# Signal_Conditioning_1.net
KiCad netlist of a schematic drawn in Altium Designer
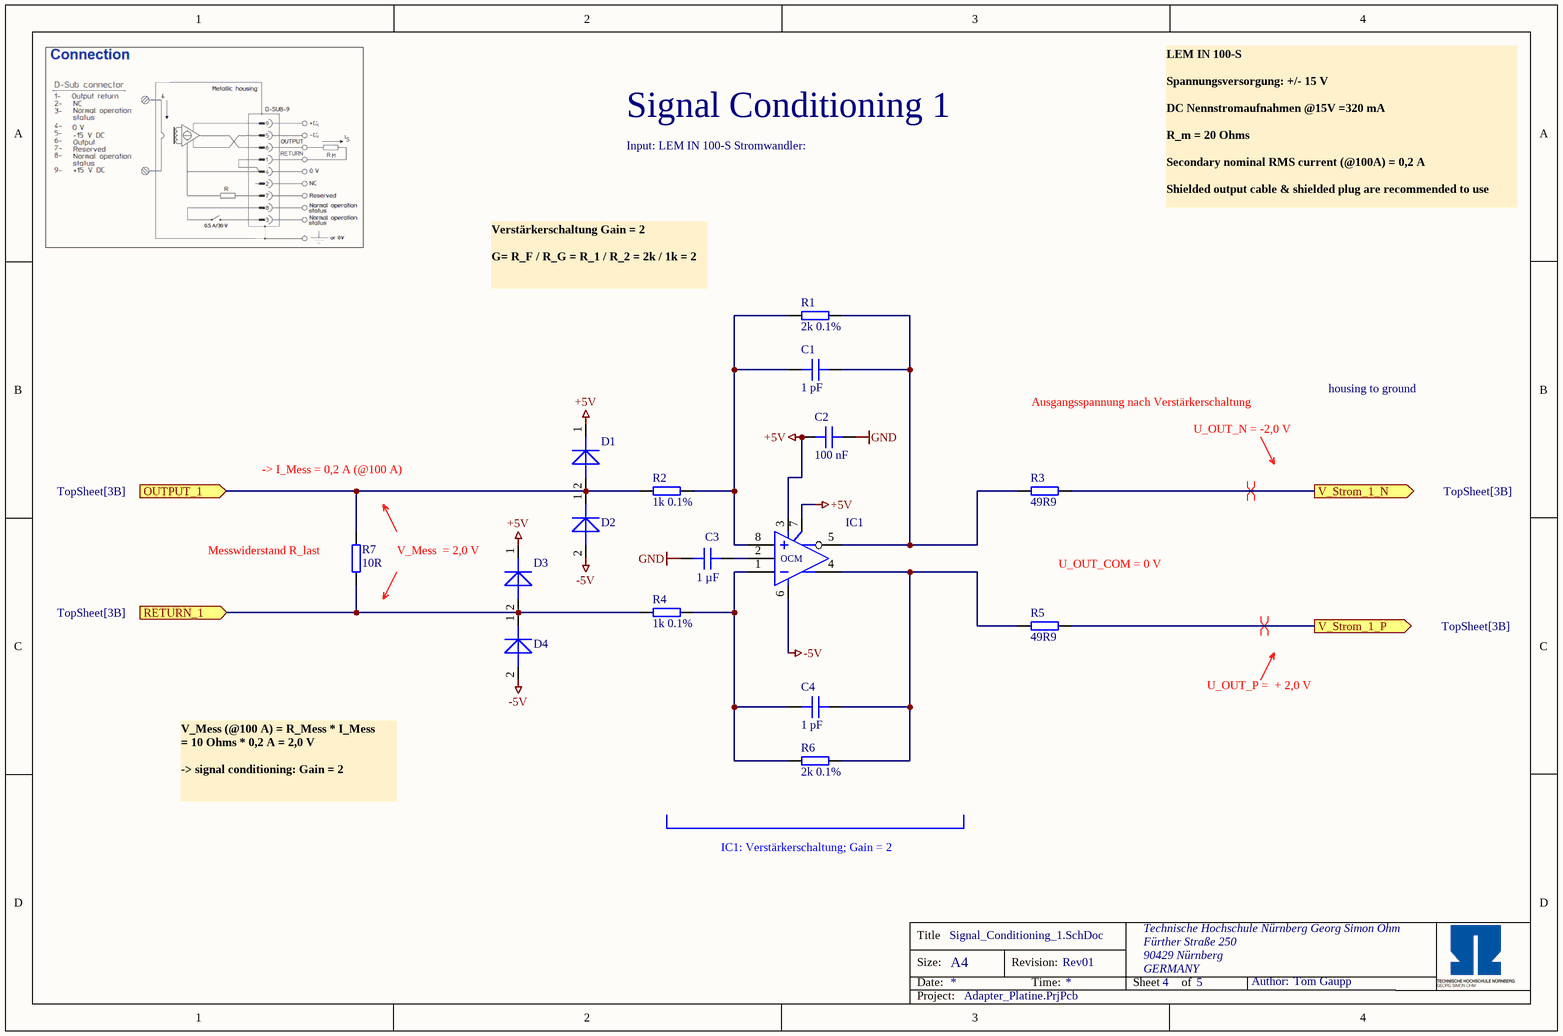
[diagram p0: Signal_Conditioning_1.SchDoc]

(export (version "E")
  (design (tool "Eeschema 10.0.6"))
  (components
    (comp (ref "C1")
      (value "1 pF")
      (footprint "C_0603")
      (description "Multilayer Ceramic Capacitors MLCC - SMD/SMT 50V 1pF C0G 0603 +/-.1pF")
      (fields
        (field (name "MANUFACTURER PART NUMBER") "KGM15ACG1H1R0BT")
        (field (name "MANUFACTURER") "KYOCERA AVX")
        (field (name "CREATED FROM") "TGaupp")
      )
      (libsource (lib "user") (part "Capacitor"))
    )
    (comp (ref "C2")
      (value "100 nF")
      (footprint "C_0603")
      (description "Capacitor 0603, 6.3 VDC, 100 nF, X5R")
      (fields
        (field (name "MANUFACTURER PART NUMBER") "C0603C104K9PACTU")
        (field (name "MANUFACTURER") "KEMET")
        (field (name "CREATED FROM") "MGremer")
      )
      (libsource (lib "user") (part "Capacitor"))
    )
    (comp (ref "C3")
      (value "1 µF")
      (footprint "C_0603")
      (description "50V 1uF X5R ±10% 0603  Multilayer Ceramic Capacitors MLCC - SMD/SMT ROHS")
      (fields
        (field (name "MANUFACTURER") "Samsung Electro-Mechanics")
        (field (name "MANUFACTURER PART NUMBER") "CL10A105KB8NNNC")
        (field (name "CREATED FROM") "MGremer")
      )
      (libsource (lib "user") (part "Capacitor"))
    )
    (comp (ref "C4")
      (value "1 pF")
      (footprint "C_0603")
      (description "Multilayer Ceramic Capacitors MLCC - SMD/SMT 50V 1pF C0G 0603 +/-.1pF")
      (fields
        (field (name "MANUFACTURER PART NUMBER") "KGM15ACG1H1R0BT")
        (field (name "MANUFACTURER") "KYOCERA AVX")
        (field (name "CREATED FROM") "TGaupp")
      )
      (libsource (lib "user") (part "Capacitor"))
    )
    (comp (ref "D1")
      (value "1SS356VMFHTE-17")
      (footprint "eigene_lib_alt:1SS356VMFHTE17")
      (description "Diode")
      (fields (field (name "MOUSER PART NUMBER") "755-1SS356VMFHTE-17"))
      (libsource (lib "SamacSys") (part "1SS356VMFHTE-17"))
    )
    (comp (ref "D2")
      (value "1SS356VMFHTE-17")
      (footprint "eigene_lib_alt:1SS356VMFHTE17")
      (description "Diode")
      (fields (field (name "MOUSER PART NUMBER") "755-1SS356VMFHTE-17"))
      (libsource (lib "SamacSys") (part "1SS356VMFHTE-17"))
    )
    (comp (ref "D3")
      (value "1SS356VMFHTE-17")
      (footprint "eigene_lib_alt:1SS356VMFHTE17")
      (description "Diode")
      (fields (field (name "MOUSER PART NUMBER") "755-1SS356VMFHTE-17"))
      (libsource (lib "SamacSys") (part "1SS356VMFHTE-17"))
    )
    (comp (ref "D4")
      (value "1SS356VMFHTE-17")
      (footprint "eigene_lib_alt:1SS356VMFHTE17")
      (description "Diode")
      (fields (field (name "MOUSER PART NUMBER") "755-1SS356VMFHTE-17"))
      (libsource (lib "SamacSys") (part "1SS356VMFHTE-17"))
    )
    (comp (ref "IC1")
      (value "ADA4940-1ARZ-R7")
      (footprint "SOIC-8-N")
      (description "Differential ADC Driver")
      (fields (field (name "MANUFACTURER") "Analog Devices") (field (name "CREATED FROM") "MGremer"))
      (libsource (lib "user") (part "ADA4940-1ARZ"))
    )
    (comp (ref "R1")
      (value "2k 0.1%")
      (footprint "RES 1206_3216")
      (description "SMD resistor 2Kohms .1% 400mW 25ppm")
      (fields
        (field (name "MANUFACTURER PART NUMBER") "TNPW12062K00BEEA")
        (field (name "MANUFACTURER") "Vishay")
        (field (name "CREATED FROM") "TGaupp")
      )
      (libsource (lib "user") (part "Resistor"))
    )
    (comp (ref "R2")
      (value "1k 0.1%")
      (footprint "RES 1206_3216")
      (description "SMD resistor 1/4W 1.0Kohm 0.1% 25ppm")
      (fields
        (field (name "MANUFACTURER PART NUMBER") "ERA-8AEB102V")
        (field (name "MANUFACTURER") "Panasonic")
        (field (name "CREATED FROM") "TGaupp")
      )
      (libsource (lib "user") (part "Resistor"))
    )
    (comp (ref "R3")
      (value "49R9")
      (footprint "RES 0603_1608")
      (description "100mW Thick Film Resistors ±100ppm/℃ ±1% 49.9Ω 0603 Chip Resistor - Surface Mount ROHS")
      (fields
        (field (name "MANUFACTURER PART NUMBER") "RC0603FR-0749R9L")
        (field (name "MANUFACTURER") "YAGEO")
        (field (name "CREATED FROM") "AGeiger")
      )
      (libsource (lib "user") (part "Resistor"))
    )
    (comp (ref "R4")
      (value "1k 0.1%")
      (footprint "RES 1206_3216")
      (description "SMD resistor 1/4W 1.0Kohm 0.1% 25ppm")
      (fields
        (field (name "MANUFACTURER PART NUMBER") "ERA-8AEB102V")
        (field (name "MANUFACTURER") "Panasonic")
        (field (name "CREATED FROM") "TGaupp")
      )
      (libsource (lib "user") (part "Resistor"))
    )
    (comp (ref "R5")
      (value "49R9")
      (footprint "RES 0603_1608")
      (description "100mW Thick Film Resistors ±100ppm/℃ ±1% 49.9Ω 0603 Chip Resistor - Surface Mount ROHS")
      (fields
        (field (name "MANUFACTURER PART NUMBER") "RC0603FR-0749R9L")
        (field (name "MANUFACTURER") "YAGEO")
        (field (name "CREATED FROM") "AGeiger")
      )
      (libsource (lib "user") (part "Resistor"))
    )
    (comp (ref "R6")
      (value "2k 0.1%")
      (footprint "RES 1206_3216")
      (description "SMD resistor 2Kohms .1% 400mW 25ppm")
      (fields
        (field (name "MANUFACTURER PART NUMBER") "TNPW12062K00BEEA")
        (field (name "MANUFACTURER") "Vishay")
        (field (name "CREATED FROM") "TGaupp")
      )
      (libsource (lib "user") (part "Resistor"))
    )
    (comp (ref "R7")
      (value "10R")
      (footprint "RES 1206_3216")
      (description "SMD 10 ohm 0.5% 0.5W")
      (fields
        (field (name "MANUFACTURER PART NUMBER") "SG73G2BTTD10R0D")
        (field (name "MANUFACTURER") "KOA Speer")
        (field (name "CREATED FROM") "TGaupp")
      )
      (libsource (lib "user") (part "Resistor"))
    )
  )
  (nets
    (net (code "1") (name "+5V") (class "Default")
      (node (ref "C2") (pin "1") (pinfunction "1_1") (pintype "passive"))
      (node (ref "D1") (pin "1") (pinfunction "K_1") (pintype "passive"))
      (node (ref "D3") (pin "1") (pinfunction "K_1") (pintype "passive"))
      (node (ref "IC1") (pin "3") (pinfunction "V+_3") (pintype "passive"))
      (node (ref "IC1") (pin "7") (pinfunction "EN_7") (pintype "passive"))
    )
    (net (code "2") (name "-5V") (class "Default")
      (node (ref "D2") (pin "2") (pinfunction "A_2") (pintype "passive"))
      (node (ref "D4") (pin "2") (pinfunction "A_2") (pintype "passive"))
      (node (ref "IC1") (pin "6") (pinfunction "V-_6") (pintype "passive"))
    )
    (net (code "3") (name "/OUTPUT_1") (class "Default")
      (node (ref "D1") (pin "2") (pinfunction "A_2") (pintype "passive"))
      (node (ref "D2") (pin "1") (pinfunction "K_1") (pintype "passive"))
      (node (ref "R2") (pin "1") (pinfunction "1_1") (pintype "passive"))
      (node (ref "R7") (pin "2") (pinfunction "2_2") (pintype "passive"))
    )
    (net (code "4") (name "/RETURN_1") (class "Default")
      (node (ref "D3") (pin "2") (pinfunction "A_2") (pintype "passive"))
      (node (ref "D4") (pin "1") (pinfunction "K_1") (pintype "passive"))
      (node (ref "R4") (pin "1") (pinfunction "1_1") (pintype "passive"))
      (node (ref "R7") (pin "1") (pinfunction "1_1") (pintype "passive"))
    )
    (net (code "5") (name "/V_Strom_1_N") (class "Default")
      (node (ref "R3") (pin "2") (pinfunction "2_2") (pintype "passive"))
    )
    (net (code "6") (name "/V_Strom_1_P") (class "Default")
      (node (ref "R5") (pin "2") (pinfunction "2_2") (pintype "passive"))
    )
    (net (code "7") (name "GND") (class "Default")
      (node (ref "C2") (pin "2") (pinfunction "2_2") (pintype "passive"))
      (node (ref "C3") (pin "1") (pinfunction "1_1") (pintype "passive"))
    )
    (net (code "8") (name "Net-(C1-Pad2)") (class "Default")
      (node (ref "C1") (pin "2") (pinfunction "2_2") (pintype "passive"))
      (node (ref "IC1") (pin "5") (pinfunction "Out_5") (pintype "passive"))
      (node (ref "R1") (pin "2") (pinfunction "2_2") (pintype "passive"))
      (node (ref "R3") (pin "1") (pinfunction "1_1") (pintype "passive"))
    )
    (net (code "9") (name "Net-(C4-Pad2)") (class "Default")
      (node (ref "C4") (pin "2") (pinfunction "2_2") (pintype "passive"))
      (node (ref "IC1") (pin "4") (pinfunction "Out_4") (pintype "passive"))
      (node (ref "R5") (pin "1") (pinfunction "1_1") (pintype "passive"))
      (node (ref "R6") (pin "2") (pinfunction "2_2") (pintype "passive"))
    )
    (net (code "10") (name "Net-(IC1-+)") (class "Default")
      (node (ref "C1") (pin "1") (pinfunction "1_1") (pintype "passive"))
      (node (ref "IC1") (pin "8") (pinfunction "+_8") (pintype "passive"))
      (node (ref "R1") (pin "1") (pinfunction "1_1") (pintype "passive"))
      (node (ref "R2") (pin "2") (pinfunction "2_2") (pintype "passive"))
    )
    (net (code "11") (name "Net-(IC1--)") (class "Default")
      (node (ref "C4") (pin "1") (pinfunction "1_1") (pintype "passive"))
      (node (ref "IC1") (pin "1") (pinfunction "-_1") (pintype "passive"))
      (node (ref "R4") (pin "2") (pinfunction "2_2") (pintype "passive"))
      (node (ref "R6") (pin "1") (pinfunction "1_1") (pintype "passive"))
    )
    (net (code "12") (name "Net-(IC1-OCM)") (class "Default")
      (node (ref "C3") (pin "2") (pinfunction "2_2") (pintype "passive"))
      (node (ref "IC1") (pin "2") (pinfunction "OCM_2") (pintype "passive"))
    )
  )
)
